# NB2_CommonMemory_Termination.net
KiCad netlist of a schematic drawn in Altium Designer
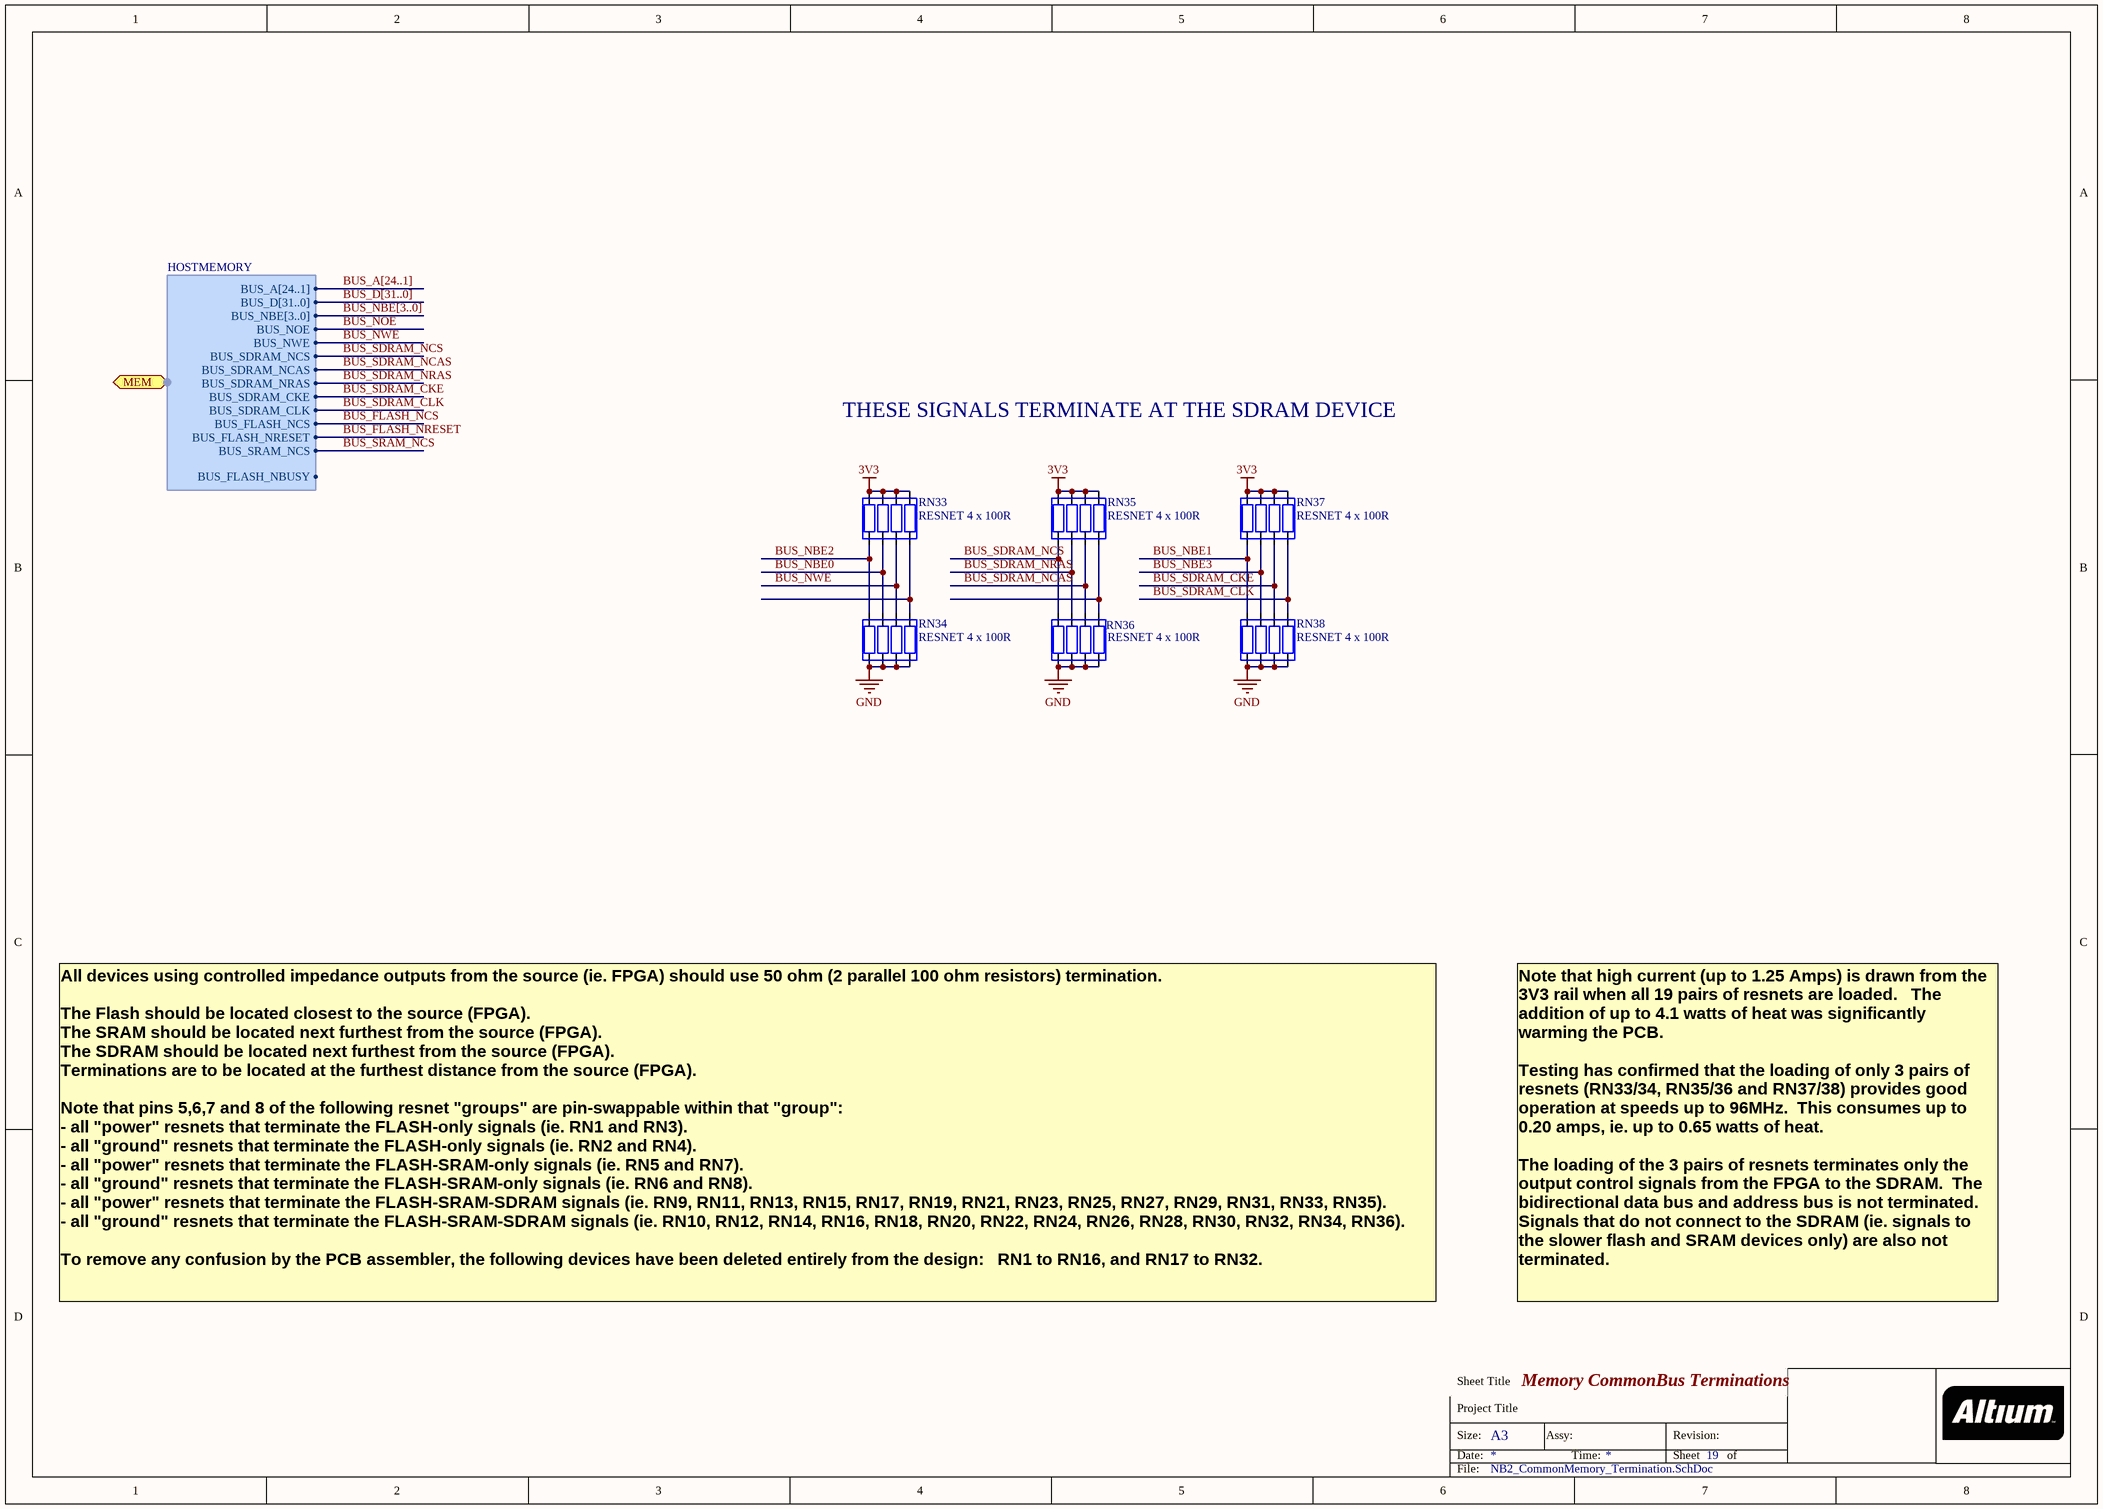
[diagram p0: NB2_CommonMemory_Termination.SchDoc]

(export (version "E")
  (design (tool "Eeschema 10.0.6"))
  (components
    (comp (ref "RN33")
      (value "RESNET 4 x 100R")
      (footprint "RESNET-1005X4")
      (description "Resistor Network, Isolated, 4 x 100R, 5%, SMD 0402 x 4")
      (fields (field (name "TOLERANCE") "5 %"))
      (libsource (lib "AltiumDesignLibrary") (part "RES-NET-IND-4-SMD"))
    )
    (comp (ref "RN34")
      (value "RESNET 4 x 100R")
      (footprint "RESNET-1005X4")
      (description "Resistor Network, Isolated, 4 x 100R, 5%, SMD 0402 x 4")
      (fields (field (name "TOLERANCE") "5 %"))
      (libsource (lib "AltiumDesignLibrary") (part "RES-NET-IND-4-SMD"))
    )
    (comp (ref "RN35")
      (value "RESNET 4 x 100R")
      (footprint "RESNET-1005X4")
      (description "Resistor Network, Isolated, 4 x 100R, 5%, SMD 0402 x 4")
      (fields (field (name "TOLERANCE") "5 %"))
      (libsource (lib "AltiumDesignLibrary") (part "RES-NET-IND-4-SMD"))
    )
    (comp (ref "RN36")
      (value "RESNET 4 x 100R")
      (footprint "RESNET-1005X4")
      (description "Resistor Network, Isolated, 4 x 100R, 5%, SMD 0402 x 4")
      (fields (field (name "TOLERANCE") "5 %"))
      (libsource (lib "AltiumDesignLibrary") (part "RES-NET-IND-4-SMD"))
    )
    (comp (ref "RN37")
      (value "RESNET 4 x 100R")
      (footprint "RESNET-1005X4")
      (description "Resistor Network, Isolated, 4 x 100R, 5%, SMD 0402 x 4")
      (fields (field (name "TOLERANCE") "5 %"))
      (libsource (lib "AltiumDesignLibrary") (part "RES-NET-IND-4-SMD"))
    )
    (comp (ref "RN38")
      (value "RESNET 4 x 100R")
      (footprint "RESNET-1005X4")
      (description "Resistor Network, Isolated, 4 x 100R, 5%, SMD 0402 x 4")
      (fields (field (name "TOLERANCE") "5 %"))
      (libsource (lib "AltiumDesignLibrary") (part "RES-NET-IND-4-SMD"))
    )
  )
  (nets
    (net (code "37") (name "/BUS_NBE0") (class "Default")
      (node (ref "RN33") (pin "6") (pinfunction "6_6") (pintype "passive"))
      (node (ref "RN34") (pin "7") (pinfunction "7_7") (pintype "passive"))
    )
    (net (code "38") (name "/BUS_NBE1") (class "Default")
      (node (ref "RN37") (pin "5") (pinfunction "5_5") (pintype "passive"))
      (node (ref "RN38") (pin "8") (pinfunction "8_8") (pintype "passive"))
    )
    (net (code "39") (name "/BUS_NBE2") (class "Default")
      (node (ref "RN33") (pin "5") (pinfunction "5_5") (pintype "passive"))
      (node (ref "RN34") (pin "8") (pinfunction "8_8") (pintype "passive"))
    )
    (net (code "40") (name "/BUS_NBE3") (class "Default")
      (node (ref "RN37") (pin "6") (pinfunction "6_6") (pintype "passive"))
      (node (ref "RN38") (pin "7") (pinfunction "7_7") (pintype "passive"))
    )
    (net (code "43") (name "/BUS_NWE") (class "Default")
      (node (ref "RN33") (pin "7") (pinfunction "7_7") (pintype "passive"))
      (node (ref "RN34") (pin "6") (pinfunction "6_6") (pintype "passive"))
    )
    (net (code "44") (name "/BUS_SDRAM_CKE") (class "Default")
      (node (ref "RN37") (pin "7") (pinfunction "7_7") (pintype "passive"))
      (node (ref "RN38") (pin "6") (pinfunction "6_6") (pintype "passive"))
    )
    (net (code "45") (name "/BUS_SDRAM_CLK") (class "Default")
      (node (ref "RN37") (pin "8") (pinfunction "8_8") (pintype "passive"))
      (node (ref "RN38") (pin "5") (pinfunction "5_5") (pintype "passive"))
    )
    (net (code "46") (name "/BUS_SDRAM_NCAS") (class "Default")
      (node (ref "RN35") (pin "7") (pinfunction "7_7") (pintype "passive"))
      (node (ref "RN36") (pin "6") (pinfunction "6_6") (pintype "passive"))
    )
    (net (code "47") (name "/BUS_SDRAM_NCS") (class "Default")
      (node (ref "RN35") (pin "5") (pinfunction "5_5") (pintype "passive"))
      (node (ref "RN36") (pin "8") (pinfunction "8_8") (pintype "passive"))
    )
    (net (code "48") (name "/BUS_SDRAM_NRAS") (class "Default")
      (node (ref "RN35") (pin "6") (pinfunction "6_6") (pintype "passive"))
      (node (ref "RN36") (pin "7") (pinfunction "7_7") (pintype "passive"))
    )
    (net (code "52") (name "3V3") (class "Default")
      (node (ref "RN33") (pin "1") (pinfunction "1_1") (pintype "passive"))
      (node (ref "RN33") (pin "2") (pinfunction "2_2") (pintype "passive"))
      (node (ref "RN33") (pin "3") (pinfunction "3_3") (pintype "passive"))
      (node (ref "RN33") (pin "4") (pinfunction "4_4") (pintype "passive"))
      (node (ref "RN35") (pin "1") (pinfunction "1_1") (pintype "passive"))
      (node (ref "RN35") (pin "2") (pinfunction "2_2") (pintype "passive"))
      (node (ref "RN35") (pin "3") (pinfunction "3_3") (pintype "passive"))
      (node (ref "RN35") (pin "4") (pinfunction "4_4") (pintype "passive"))
      (node (ref "RN37") (pin "1") (pinfunction "1_1") (pintype "passive"))
      (node (ref "RN37") (pin "2") (pinfunction "2_2") (pintype "passive"))
      (node (ref "RN37") (pin "3") (pinfunction "3_3") (pintype "passive"))
      (node (ref "RN37") (pin "4") (pinfunction "4_4") (pintype "passive"))
    )
    (net (code "53") (name "GND") (class "Default")
      (node (ref "RN34") (pin "1") (pinfunction "1_1") (pintype "passive"))
      (node (ref "RN34") (pin "2") (pinfunction "2_2") (pintype "passive"))
      (node (ref "RN34") (pin "3") (pinfunction "3_3") (pintype "passive"))
      (node (ref "RN34") (pin "4") (pinfunction "4_4") (pintype "passive"))
      (node (ref "RN36") (pin "1") (pinfunction "1_1") (pintype "passive"))
      (node (ref "RN36") (pin "2") (pinfunction "2_2") (pintype "passive"))
      (node (ref "RN36") (pin "3") (pinfunction "3_3") (pintype "passive"))
      (node (ref "RN36") (pin "4") (pinfunction "4_4") (pintype "passive"))
      (node (ref "RN38") (pin "1") (pinfunction "1_1") (pintype "passive"))
      (node (ref "RN38") (pin "2") (pinfunction "2_2") (pintype "passive"))
      (node (ref "RN38") (pin "3") (pinfunction "3_3") (pintype "passive"))
      (node (ref "RN38") (pin "4") (pinfunction "4_4") (pintype "passive"))
    )
    (net (code "54") (name "Net-(RN33-Pad8)") (class "Default")
      (node (ref "RN33") (pin "8") (pinfunction "8_8") (pintype "passive"))
      (node (ref "RN34") (pin "5") (pinfunction "5_5") (pintype "passive"))
    )
    (net (code "55") (name "Net-(RN35-Pad8)") (class "Default")
      (node (ref "RN35") (pin "8") (pinfunction "8_8") (pintype "passive"))
      (node (ref "RN36") (pin "5") (pinfunction "5_5") (pintype "passive"))
    )
  )
)
